# SECO_mobo_header.net
KiCad netlist of a schematic drawn in Altium Designer
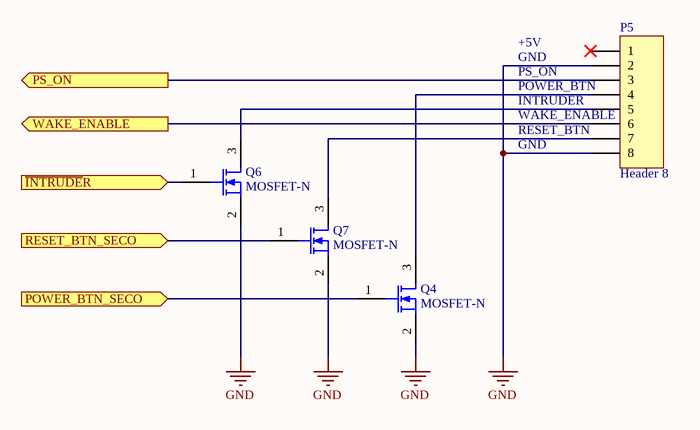
[diagram p0: SECO mobo header.SchDoc]

(export (version "E")
  (design (tool "Eeschema 10.0.6"))
  (components
    (comp (ref "P5")
      (value "Header 8")
      (footprint "S08B-PASK-2")
      (description "Header, 8-Pin")
      (fields (field (name "PUBLISHER") "Altium Limited"))
      (libsource (lib "Miscellaneous Connectors") (part "Header 8"))
    )
    (comp (ref "Q4")
      (value "MOSFET-N")
      (footprint "2N7002")
      (description "N-Channel MOSFET")
      (fields (field (name "PUBLISHER") "Altium Limited"))
      (libsource (lib "Miscellaneous Devices") (part "MOSFET-N"))
    )
    (comp (ref "Q6")
      (value "MOSFET-N")
      (footprint "2N7002")
      (description "N-Channel MOSFET")
      (fields (field (name "PUBLISHER") "Altium Limited"))
      (libsource (lib "Miscellaneous Devices") (part "MOSFET-N"))
    )
    (comp (ref "Q7")
      (value "MOSFET-N")
      (footprint "2N7002")
      (description "N-Channel MOSFET")
      (fields (field (name "PUBLISHER") "Altium Limited"))
      (libsource (lib "Miscellaneous Devices") (part "MOSFET-N"))
    )
  )
  (nets
    (net (code "1") (name "/POWER_BTN_SECO") (class "Default")
      (node (ref "Q4") (pin "1") (pinfunction "G_1") (pintype "passive"))
    )
    (net (code "2") (name "/PS_ON") (class "Default")
      (node (ref "P5") (pin "3") (pinfunction "3_3") (pintype "passive"))
    )
    (net (code "3") (name "/RESET_BTN_SECO") (class "Default")
      (node (ref "Q7") (pin "1") (pinfunction "G_1") (pintype "passive"))
    )
    (net (code "4") (name "/WAKE_ENABLE") (class "Default")
      (node (ref "P5") (pin "6") (pinfunction "6_6") (pintype "passive"))
    )
    (net (code "5") (name "/~{INTRUDE}R") (class "Default")
      (node (ref "Q6") (pin "1") (pinfunction "G_1") (pintype "passive"))
    )
    (net (code "6") (name "GND") (class "Default")
      (node (ref "P5") (pin "2") (pinfunction "2_2") (pintype "passive"))
      (node (ref "P5") (pin "8") (pinfunction "8_8") (pintype "passive"))
      (node (ref "Q4") (pin "2") (pinfunction "S_2") (pintype "passive"))
      (node (ref "Q6") (pin "2") (pinfunction "S_2") (pintype "passive"))
      (node (ref "Q7") (pin "2") (pinfunction "S_2") (pintype "passive"))
    )
    (net (code "7") (name "Net-(Q4-D)") (class "Default")
      (node (ref "P5") (pin "4") (pinfunction "4_4") (pintype "passive"))
      (node (ref "Q4") (pin "3") (pinfunction "D_3") (pintype "passive"))
    )
    (net (code "8") (name "Net-(Q6-D)") (class "Default")
      (node (ref "P5") (pin "5") (pinfunction "5_5") (pintype "passive"))
      (node (ref "Q6") (pin "3") (pinfunction "D_3") (pintype "passive"))
    )
    (net (code "9") (name "Net-(Q7-D)") (class "Default")
      (node (ref "P5") (pin "7") (pinfunction "7_7") (pintype "passive"))
      (node (ref "Q7") (pin "3") (pinfunction "D_3") (pintype "passive"))
    )
    (net (code "10") (name "unconnected-(P5-Pad1)") (class "Default")
      (node (ref "P5") (pin "1") (pinfunction "1_1") (pintype "passive+no_connect"))
    )
  )
)
